# MG2639_Cellular_Shield.net
KiCad netlist of a schematic drawn in EAGLE
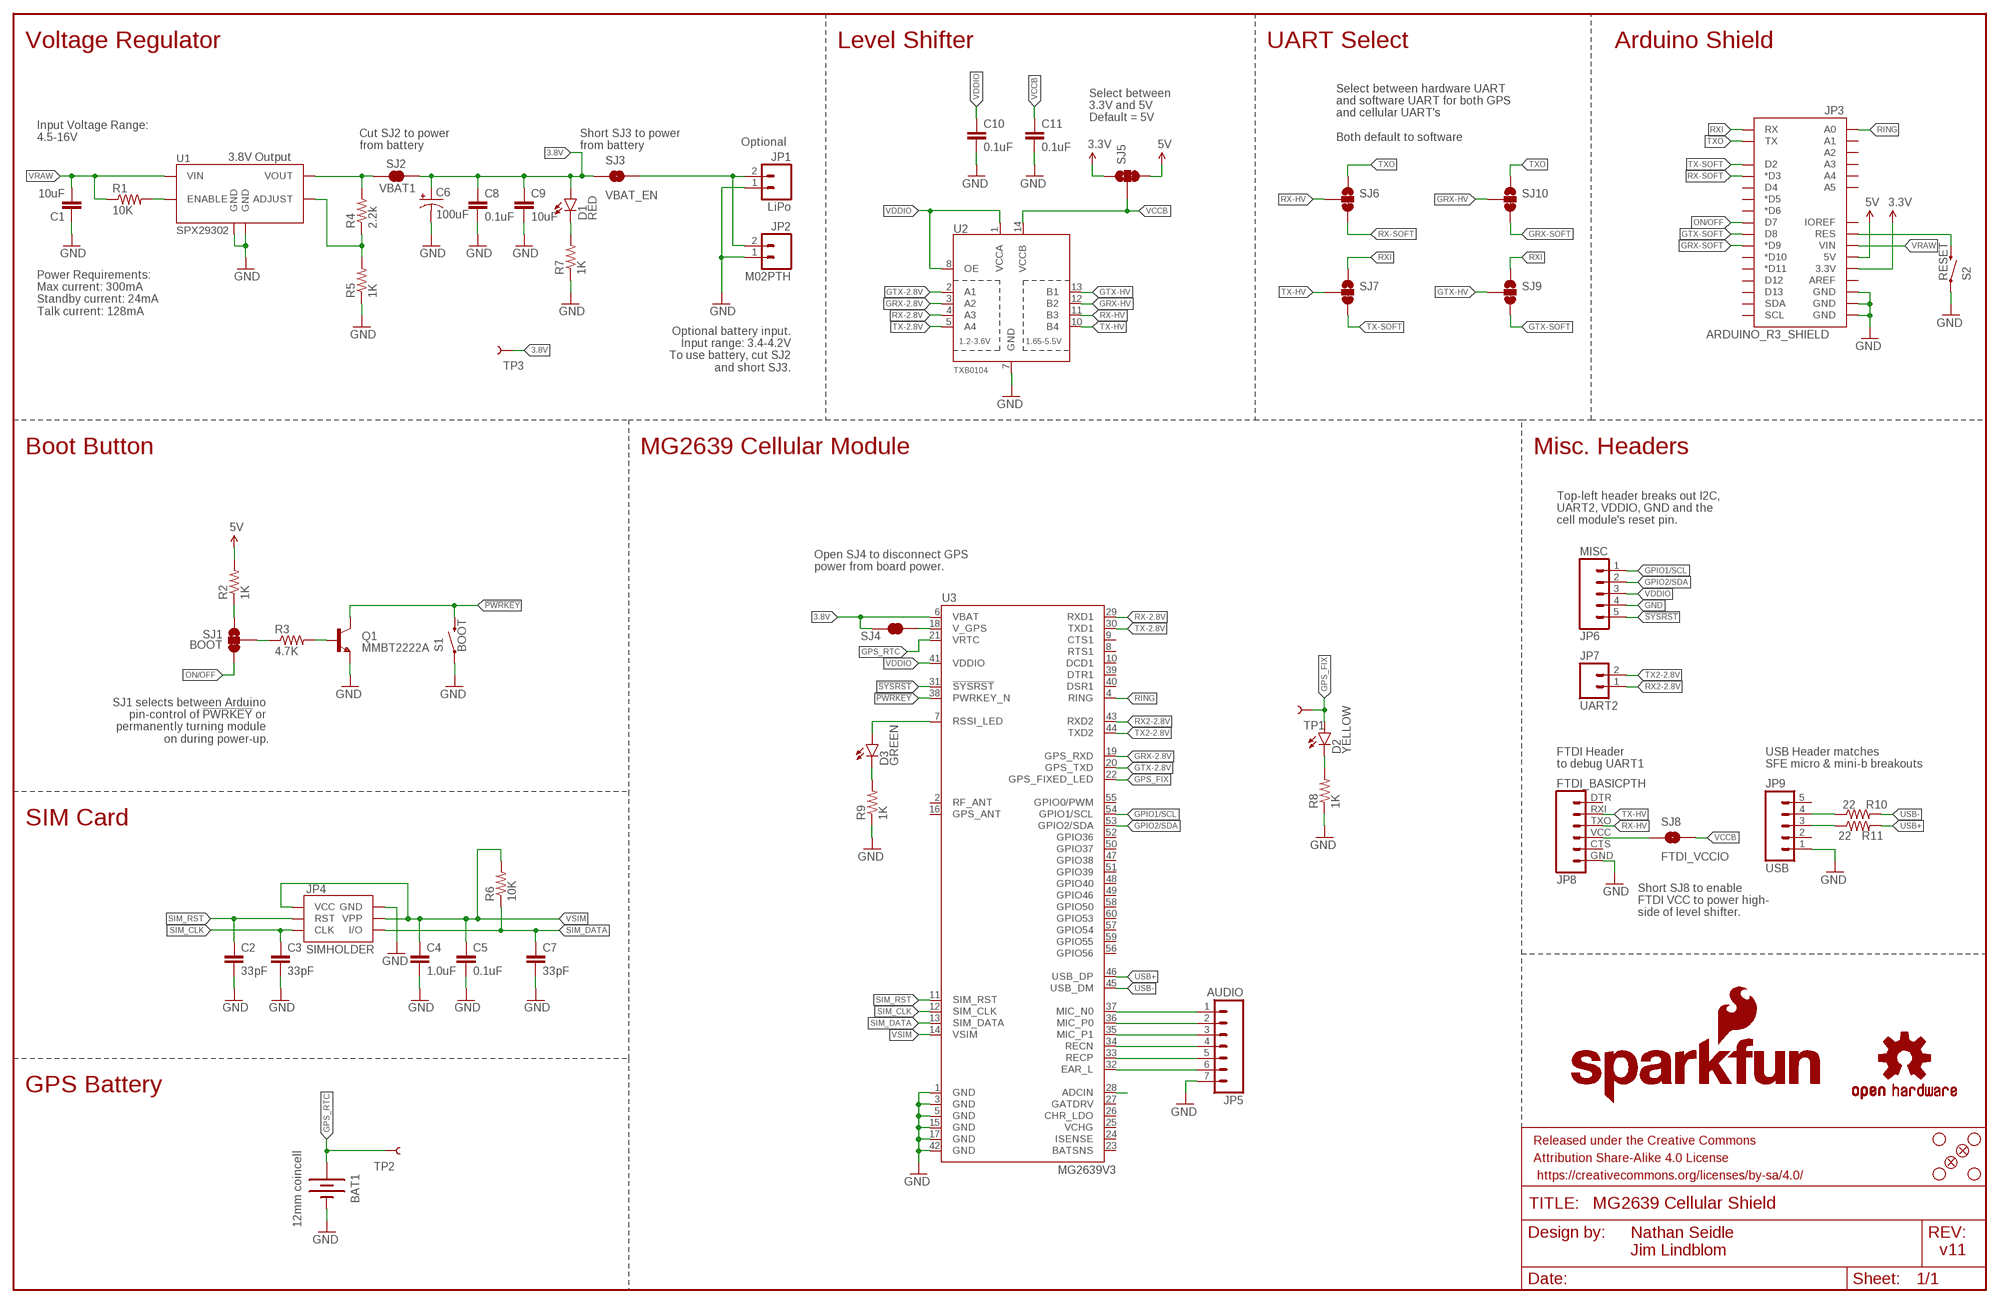
[diagram p0: schematic, sheet 1]

(export (version "E")
  (design (tool "Eeschema 10.0.6"))
  (components
    (comp (ref "BAT1")
      (value "12mm coincell")
      (footprint "eagle-import:BATTCON_12MM")
      (libsource (lib "eagle-import") (part "BATTERY12MM"))
    )
    (comp (ref "C1")
      (value "10uF")
      (footprint "eagle-import:1210")
      (libsource (lib "eagle-import") (part "10UF50V20%(1210)"))
    )
    (comp (ref "C2")
      (value "33pF")
      (footprint "eagle-import:0603-CAP")
      (libsource (lib "eagle-import") (part "33PF-50V-5%-(0603)"))
    )
    (comp (ref "C3")
      (value "33pF")
      (footprint "eagle-import:0603-CAP")
      (libsource (lib "eagle-import") (part "33PF-50V-5%-(0603)"))
    )
    (comp (ref "C4")
      (value "1.0uF")
      (footprint "eagle-import:0603-CAP")
      (libsource (lib "eagle-import") (part "1.0UF-16V-10%(0603)"))
    )
    (comp (ref "C5")
      (value "0.1uF")
      (footprint "eagle-import:0603-CAP")
      (libsource (lib "eagle-import") (part "0.1UF-25V(+80/-20%)(0603)"))
    )
    (comp (ref "C6")
      (value "100uF")
      (footprint "eagle-import:EIA7343")
      (libsource (lib "eagle-import") (part "100UF-10V-10%(TANT)"))
    )
    (comp (ref "C7")
      (value "33pF")
      (footprint "eagle-import:0603-CAP")
      (libsource (lib "eagle-import") (part "33PF-50V-5%-(0603)"))
    )
    (comp (ref "C8")
      (value "0.1uF")
      (footprint "eagle-import:0603-CAP")
      (libsource (lib "eagle-import") (part "0.1UF-25V(+80/-20%)(0603)"))
    )
    (comp (ref "C9")
      (value "10uF")
      (footprint "eagle-import:1210")
      (libsource (lib "eagle-import") (part "10UF50V20%(1210)"))
    )
    (comp (ref "C10")
      (value "0.1uF")
      (footprint "eagle-import:0603-CAP")
      (libsource (lib "eagle-import") (part "0.1UF-25V(+80/-20%)(0603)"))
    )
    (comp (ref "C11")
      (value "0.1uF")
      (footprint "eagle-import:0603-CAP")
      (libsource (lib "eagle-import") (part "0.1UF-25V(+80/-20%)(0603)"))
    )
    (comp (ref "D1")
      (value "RED")
      (footprint "eagle-import:LED-1206")
      (libsource (lib "eagle-import") (part "LED-RED1206"))
    )
    (comp (ref "D2")
      (value "YELLOW")
      (footprint "eagle-import:LED-1206")
      (libsource (lib "eagle-import") (part "LED-YELLOWLARGE"))
    )
    (comp (ref "D3")
      (value "GREEN")
      (footprint "eagle-import:LED-1206")
      (libsource (lib "eagle-import") (part "LED-GREENLARGE"))
    )
    (comp (ref "FID1")
      (value "FIDUCIAL1X2")
      (footprint "eagle-import:FIDUCIAL-1X2")
      (libsource (lib "eagle-import") (part "FIDUCIAL1X2"))
    )
    (comp (ref "FID2")
      (value "FIDUCIAL1X2")
      (footprint "eagle-import:FIDUCIAL-1X2")
      (libsource (lib "eagle-import") (part "FIDUCIAL1X2"))
    )
    (comp (ref "FRAME1")
      (value "FRAME-LEDGER")
      (footprint "eagle-import:CREATIVE_COMMONS")
      (libsource (lib "eagle-import") (part "FRAME-LEDGER"))
    )
    (comp (ref "JP1")
      (value "LiPo")
      (footprint "eagle-import:JST-2-PTH")
      (libsource (lib "eagle-import") (part "M02JST-PTH-2"))
    )
    (comp (ref "JP2")
      (value "M02PTH")
      (footprint "eagle-import:1X02")
      (libsource (lib "eagle-import") (part "M02PTH"))
    )
    (comp (ref "JP3")
      (value "ARDUINO_R3_SHIELD")
      (footprint "eagle-import:UNO_R3_SHIELD_NOLABELS")
      (libsource (lib "eagle-import") (part "ARDUINO_R3_SHIELDNOLABELS"))
    )
    (comp (ref "JP4")
      (value "SIMHOLDER")
      (footprint "eagle-import:SIMHOLDER")
      (libsource (lib "eagle-import") (part "SIMHOLDERSIM"))
    )
    (comp (ref "JP5")
      (value "AUDIO")
      (footprint "eagle-import:1X07")
      (libsource (lib "eagle-import") (part "M07"))
    )
    (comp (ref "JP6")
      (value "MISC")
      (footprint "eagle-import:1X05")
      (libsource (lib "eagle-import") (part "M05PTH"))
    )
    (comp (ref "JP7")
      (value "UART2")
      (footprint "eagle-import:1X02")
      (libsource (lib "eagle-import") (part "M02PTH"))
    )
    (comp (ref "JP8")
      (value "FTDI_BASICPTH")
      (footprint "eagle-import:FTDI_BASIC")
      (libsource (lib "eagle-import") (part "FTDI_BASICPTH"))
    )
    (comp (ref "JP9")
      (value "USB")
      (footprint "eagle-import:1X05")
      (libsource (lib "eagle-import") (part "M05PTH"))
    )
    (comp (ref "LOGO1")
      (value "SFE_LOGO_NAME.1_INCH")
      (footprint "eagle-import:SFE_LOGO_NAME_.1")
      (libsource (lib "eagle-import") (part "SFE_LOGO_NAME.1_INCH"))
    )
    (comp (ref "LOGO2")
      (value "SFE_LOGO_NAME_FLAME.2_INCH")
      (footprint "eagle-import:SFE_LOGO_NAME_FLAME_.2")
      (libsource (lib "eagle-import") (part "SFE_LOGO_NAME_FLAME.2_INCH"))
    )
    (comp (ref "LOGO3")
      (value "OSHW-LOGOS")
      (footprint "eagle-import:OSHW-LOGO-S")
      (libsource (lib "eagle-import") (part "OSHW-LOGOS"))
    )
    (comp (ref "Q1")
      (value "MMBT2222A")
      (footprint "eagle-import:SOT23-3")
      (libsource (lib "eagle-import") (part "TRANSISTOR_NPNMMBT2222A"))
    )
    (comp (ref "R1")
      (value "10K")
      (footprint "eagle-import:0603-RES")
      (libsource (lib "eagle-import") (part "10KOHM1/10W1%(0603)0603"))
    )
    (comp (ref "R2")
      (value "1K")
      (footprint "eagle-import:0603-RES")
      (libsource (lib "eagle-import") (part "1KOHM1/10W1%(0603)"))
    )
    (comp (ref "R3")
      (value "4.7K")
      (footprint "eagle-import:0603")
      (libsource (lib "eagle-import") (part "4.7KOHM1/10W1%(0603)"))
    )
    (comp (ref "R4")
      (value "2.2k")
      (footprint "eagle-import:0603-RES")
      (libsource (lib "eagle-import") (part "2.2KOHM1/10W1%(0603)"))
    )
    (comp (ref "R5")
      (value "1K")
      (footprint "eagle-import:0603-RES")
      (libsource (lib "eagle-import") (part "1KOHM1/10W1%(0603)"))
    )
    (comp (ref "R6")
      (value "10K")
      (footprint "eagle-import:0603-RES")
      (libsource (lib "eagle-import") (part "10KOHM1/10W1%(0603)0603"))
    )
    (comp (ref "R7")
      (value "1K")
      (footprint "eagle-import:0603-RES")
      (libsource (lib "eagle-import") (part "1KOHM1/10W1%(0603)"))
    )
    (comp (ref "R8")
      (value "1K")
      (footprint "eagle-import:0603-RES")
      (libsource (lib "eagle-import") (part "1KOHM1/10W1%(0603)"))
    )
    (comp (ref "R9")
      (value "1K")
      (footprint "eagle-import:0603-RES")
      (libsource (lib "eagle-import") (part "1KOHM1/10W1%(0603)"))
    )
    (comp (ref "R10")
      (value "22")
      (footprint "eagle-import:0603-RES")
      (libsource (lib "eagle-import") (part "22OHM1/10W1%(0603)"))
    )
    (comp (ref "R11")
      (value "22")
      (footprint "eagle-import:0603-RES")
      (libsource (lib "eagle-import") (part "22OHM1/10W1%(0603)"))
    )
    (comp (ref "S1")
      (value "BOOT")
      (footprint "eagle-import:TACTILE-SWITCH-SMD")
      (libsource (lib "eagle-import") (part "SWITCH-MOMENTARY-2SMD"))
    )
    (comp (ref "S2")
      (value "RESET")
      (footprint "eagle-import:TACTILE-SWITCH-SMD")
      (libsource (lib "eagle-import") (part "SWITCH-MOMENTARY-2SMD"))
    )
    (comp (ref "SJ1")
      (value "BOOT")
      (footprint "eagle-import:PAD-JUMPER-3-2OF3_NC_BY_TRACE_YES_SILK_FULL_BOX")
      (libsource (lib "eagle-import") (part "JUMPER-PAD-3-2OF3_NC_BY_TRACE"))
    )
    (comp (ref "SJ2")
      (value "VBAT1")
      (footprint "eagle-import:PAD-JUMPER-2-NC_BY_TRACE_YES_SILK")
      (libsource (lib "eagle-import") (part "JUMPER-PAD-2-NC_BY_TRACE"))
    )
    (comp (ref "SJ3")
      (value "VBAT_EN")
      (footprint "eagle-import:PAD-JUMPER-2-NO_YES_SILK")
      (libsource (lib "eagle-import") (part "JUMPER-PAD-2-NOYES_SILK"))
    )
    (comp (ref "SJ4")
      (value "JUMPER-PAD-2-NC_BY_TRACE")
      (footprint "eagle-import:PAD-JUMPER-2-NC_BY_TRACE_YES_SILK")
      (libsource (lib "eagle-import") (part "JUMPER-PAD-2-NC_BY_TRACE"))
    )
    (comp (ref "SJ5")
      (value "JUMPER-PAD-3-2OF3_NC_BY_TRACE")
      (footprint "eagle-import:PAD-JUMPER-3-2OF3_NC_BY_TRACE_YES_SILK_FULL_BOX")
      (libsource (lib "eagle-import") (part "JUMPER-PAD-3-2OF3_NC_BY_TRACE"))
    )
    (comp (ref "SJ6")
      (value "JUMPER-PAD-3-2OF3_NC_BY_TRACE")
      (footprint "eagle-import:PAD-JUMPER-3-2OF3_NC_BY_TRACE_YES_SILK_FULL_BOX")
      (libsource (lib "eagle-import") (part "JUMPER-PAD-3-2OF3_NC_BY_TRACE"))
    )
    (comp (ref "SJ7")
      (value "JUMPER-PAD-3-2OF3_NC_BY_TRACE")
      (footprint "eagle-import:PAD-JUMPER-3-2OF3_NC_BY_TRACE_YES_SILK_FULL_BOX")
      (libsource (lib "eagle-import") (part "JUMPER-PAD-3-2OF3_NC_BY_TRACE"))
    )
    (comp (ref "SJ8")
      (value "FTDI_VCCIO")
      (footprint "eagle-import:PAD-JUMPER-2-NO_YES_SILK")
      (libsource (lib "eagle-import") (part "JUMPER-PAD-2-NOYES_SILK"))
    )
    (comp (ref "SJ9")
      (value "JUMPER-PAD-3-2OF3_NC_BY_TRACE")
      (footprint "eagle-import:PAD-JUMPER-3-2OF3_NC_BY_TRACE_YES_SILK_FULL_BOX")
      (libsource (lib "eagle-import") (part "JUMPER-PAD-3-2OF3_NC_BY_TRACE"))
    )
    (comp (ref "SJ10")
      (value "JUMPER-PAD-3-2OF3_NC_BY_TRACE")
      (footprint "eagle-import:PAD-JUMPER-3-2OF3_NC_BY_TRACE_YES_SILK_FULL_BOX")
      (libsource (lib "eagle-import") (part "JUMPER-PAD-3-2OF3_NC_BY_TRACE"))
    )
    (comp (ref "STANDOFF1")
      (value "STAND-OFF")
      (footprint "eagle-import:STAND-OFF")
      (libsource (lib "eagle-import") (part "STAND-OFF"))
    )
    (comp (ref "STANDOFF2")
      (value "STAND-OFF")
      (footprint "eagle-import:STAND-OFF")
      (libsource (lib "eagle-import") (part "STAND-OFF"))
    )
    (comp (ref "STANDOFF3")
      (value "STAND-OFF")
      (footprint "eagle-import:STAND-OFF")
      (libsource (lib "eagle-import") (part "STAND-OFF"))
    )
    (comp (ref "STANDOFF4")
      (value "STAND-OFF")
      (footprint "eagle-import:STAND-OFF")
      (libsource (lib "eagle-import") (part "STAND-OFF"))
    )
    (comp (ref "TP1")
      (value "TEST-POINT3X5")
      (footprint "eagle-import:PAD.03X.05")
      (libsource (lib "eagle-import") (part "TEST-POINT3X5"))
    )
    (comp (ref "TP2")
      (value "TEST-POINT3X5")
      (footprint "eagle-import:PAD.03X.05")
      (libsource (lib "eagle-import") (part "TEST-POINT3X5"))
    )
    (comp (ref "TP3")
      (value "TEST-POINT3X5")
      (footprint "eagle-import:PAD.03X.05")
      (libsource (lib "eagle-import") (part "TEST-POINT3X5"))
    )
    (comp (ref "U1")
      (value "SPX29302")
      (footprint "eagle-import:Q5-DD_SPX29300")
      (libsource (lib "eagle-import") (part "SPX29302"))
    )
    (comp (ref "U2")
      (value "TXB0104")
      (footprint "eagle-import:SO14")
      (libsource (lib "eagle-import") (part "TXB0104PWRSOIC14"))
    )
    (comp (ref "U3")
      (value "MG2639V3")
      (footprint "eagle-import:MG2639")
      (libsource (lib "eagle-import") (part "MG2639V3"))
    )
  )
  (nets
    (net (code "1") (name "/VCHG") (class "Default")
      (node (ref "U3") (pin "25") (pinfunction "VCHG_25") (pintype "power_in"))
    )
    (net (code "2") (name "/~{PWRKEY}") (class "Default")
      (node (ref "Q1") (pin "3") (pinfunction "C_3") (pintype "passive"))
      (node (ref "S1") (pin "3") (pinfunction "2_3") (pintype "passive"))
      (node (ref "U3") (pin "38") (pinfunction "PWRKEY_N_38") (pintype "input"))
    )
    (net (code "3") (name "/~{SYSRST}") (class "Default")
      (node (ref "JP6") (pin "5") (pinfunction "5_5") (pintype "passive"))
      (node (ref "U3") (pin "31") (pinfunction "~{SYSRST}_31") (pintype "input"))
    )
    (net (code "4") (name "3.3V") (class "Default")
      (node (ref "JP3") (pin "3.3V") (pinfunction "3.3V_3.3V") (pintype "bidirectional"))
      (node (ref "SJ5") (pin "1") (pinfunction "1_1") (pintype "passive"))
    )
    (net (code "5") (name "3.8V") (class "Default")
      (node (ref "C6") (pin "A") (pinfunction "+_A") (pintype "passive"))
      (node (ref "C8") (pin "1") (pinfunction "1_1") (pintype "passive"))
      (node (ref "C9") (pin "1") (pinfunction "1_1") (pintype "passive"))
      (node (ref "D1") (pin "A") (pinfunction "A_A") (pintype "passive"))
      (node (ref "SJ2") (pin "2") (pinfunction "2_2") (pintype "passive"))
      (node (ref "SJ3") (pin "1") (pinfunction "1_1") (pintype "passive"))
      (node (ref "SJ4") (pin "1") (pinfunction "1_1") (pintype "passive"))
      (node (ref "TP3") (pin "P$1") (pinfunction "1_P$1") (pintype "bidirectional"))
      (node (ref "U3") (pin "6") (pinfunction "VBAT_6") (pintype "power_in"))
    )
    (net (code "6") (name "5V") (class "Default")
      (node (ref "JP3") (pin "5V") (pinfunction "5V_5V") (pintype "bidirectional"))
      (node (ref "R2") (pin "2") (pinfunction "2_2") (pintype "passive"))
      (node (ref "SJ5") (pin "3") (pinfunction "3_3") (pintype "passive"))
    )
    (net (code "7") (name "GND") (class "Default")
      (node (ref "BAT1") (pin "GND") (pinfunction "-_GND") (pintype "power_in"))
      (node (ref "C1") (pin "1") (pinfunction "1_1") (pintype "passive"))
      (node (ref "C10") (pin "2") (pinfunction "2_2") (pintype "passive"))
      (node (ref "C11") (pin "2") (pinfunction "2_2") (pintype "passive"))
      (node (ref "C2") (pin "2") (pinfunction "2_2") (pintype "passive"))
      (node (ref "C3") (pin "2") (pinfunction "2_2") (pintype "passive"))
      (node (ref "C4") (pin "2") (pinfunction "2_2") (pintype "passive"))
      (node (ref "C5") (pin "2") (pinfunction "2_2") (pintype "passive"))
      (node (ref "C6") (pin "C") (pinfunction "-_C") (pintype "passive"))
      (node (ref "C7") (pin "2") (pinfunction "2_2") (pintype "passive"))
      (node (ref "C8") (pin "2") (pinfunction "2_2") (pintype "passive"))
      (node (ref "C9") (pin "2") (pinfunction "2_2") (pintype "passive"))
      (node (ref "JP1") (pin "1") (pinfunction "1_1") (pintype "passive"))
      (node (ref "JP2") (pin "1") (pinfunction "1_1") (pintype "passive"))
      (node (ref "JP3") (pin "GND@0") (pinfunction "GND_GND@0") (pintype "bidirectional"))
      (node (ref "JP3") (pin "GND@1") (pinfunction "GND_GND@1") (pintype "bidirectional"))
      (node (ref "JP3") (pin "GND@2") (pinfunction "GND_GND@2") (pintype "bidirectional"))
      (node (ref "JP4") (pin "C5") (pinfunction "GND_C5") (pintype "power_in"))
      (node (ref "JP5") (pin "7") (pinfunction "7_7") (pintype "passive"))
      (node (ref "JP6") (pin "4") (pinfunction "4_4") (pintype "passive"))
      (node (ref "JP8") (pin "GND") (pinfunction "6_GND") (pintype "passive"))
      (node (ref "JP9") (pin "1") (pinfunction "1_1") (pintype "passive"))
      (node (ref "Q1") (pin "2") (pinfunction "E_2") (pintype "passive"))
      (node (ref "R5") (pin "1") (pinfunction "1_1") (pintype "passive"))
      (node (ref "R7") (pin "1") (pinfunction "1_1") (pintype "passive"))
      (node (ref "R8") (pin "1") (pinfunction "1_1") (pintype "passive"))
      (node (ref "R9") (pin "1") (pinfunction "1_1") (pintype "passive"))
      (node (ref "S1") (pin "1") (pinfunction "1_1") (pintype "passive"))
      (node (ref "S2") (pin "1") (pinfunction "1_1") (pintype "passive"))
      (node (ref "U1") (pin "3") (pinfunction "GND_3") (pintype "bidirectional"))
      (node (ref "U1") (pin "6") (pinfunction "GND_6") (pintype "bidirectional"))
      (node (ref "U2") (pin "7") (pinfunction "GND_7") (pintype "bidirectional"))
      (node (ref "U3") (pin "1") (pinfunction "GND_1") (pintype "power_in"))
      (node (ref "U3") (pin "15") (pinfunction "GND_15") (pintype "power_in"))
      (node (ref "U3") (pin "17") (pinfunction "GND_17") (pintype "power_in"))
      (node (ref "U3") (pin "3") (pinfunction "GND_3") (pintype "power_in"))
      (node (ref "U3") (pin "42") (pinfunction "GND_42") (pintype "power_in"))
      (node (ref "U3") (pin "5") (pinfunction "GND_5") (pintype "power_in"))
    )
    (net (code "8") (name "GPIO1{slash}SCL") (class "Default")
      (node (ref "JP6") (pin "1") (pinfunction "1_1") (pintype "passive"))
      (node (ref "U3") (pin "54") (pinfunction "GPIO1/SCL_54") (pintype "bidirectional"))
    )
    (net (code "9") (name "GPIO2{slash}SDA") (class "Default")
      (node (ref "JP6") (pin "2") (pinfunction "2_2") (pintype "passive"))
      (node (ref "U3") (pin "53") (pinfunction "GPIO2/SDA_53") (pintype "bidirectional"))
    )
    (net (code "10") (name "GPS_FIX") (class "Default")
      (node (ref "D2") (pin "A") (pinfunction "A_A") (pintype "passive"))
      (node (ref "TP1") (pin "P$1") (pinfunction "1_P$1") (pintype "bidirectional"))
      (node (ref "U3") (pin "22") (pinfunction "GPS_FIXED_LED_22") (pintype "output"))
    )
    (net (code "11") (name "GPS_RTC") (class "Default")
      (node (ref "BAT1") (pin "PWR@1") (pinfunction "+_PWR@1") (pintype "power_in"))
      (node (ref "TP2") (pin "P$1") (pinfunction "1_P$1") (pintype "bidirectional"))
      (node (ref "U3") (pin "21") (pinfunction "VRTC_21") (pintype "power_in"))
    )
    (net (code "12") (name "GRX-2.8V") (class "Default")
      (node (ref "U2") (pin "3") (pinfunction "A2_3") (pintype "bidirectional"))
      (node (ref "U3") (pin "19") (pinfunction "GPS_RXD_19") (pintype "input"))
    )
    (net (code "13") (name "GRX-HV") (class "Default")
      (node (ref "SJ10") (pin "2") (pinfunction "2_2") (pintype "passive"))
      (node (ref "U2") (pin "12") (pinfunction "B2_12") (pintype "bidirectional"))
    )
    (net (code "14") (name "GRX-SOFT") (class "Default")
      (node (ref "JP3") (pin "D9") (pinfunction "*D9_D9") (pintype "bidirectional"))
      (node (ref "SJ10") (pin "3") (pinfunction "3_3") (pintype "passive"))
    )
    (net (code "15") (name "GTX-2.8V") (class "Default")
      (node (ref "U2") (pin "2") (pinfunction "A1_2") (pintype "bidirectional"))
      (node (ref "U3") (pin "20") (pinfunction "GPS_TXD_20") (pintype "output"))
    )
    (net (code "16") (name "GTX-HV") (class "Default")
      (node (ref "SJ9") (pin "2") (pinfunction "2_2") (pintype "passive"))
      (node (ref "U2") (pin "13") (pinfunction "B1_13") (pintype "bidirectional"))
    )
    (net (code "17") (name "GTX-SOFT") (class "Default")
      (node (ref "JP3") (pin "D8") (pinfunction "D8_D8") (pintype "bidirectional"))
      (node (ref "SJ9") (pin "3") (pinfunction "3_3") (pintype "passive"))
    )
    (net (code "18") (name "Net-(D1-PadC)") (class "Default")
      (node (ref "D1") (pin "C") (pinfunction "C_C") (pintype "passive"))
      (node (ref "R7") (pin "2") (pinfunction "2_2") (pintype "passive"))
    )
    (net (code "19") (name "Net-(D2-PadC)") (class "Default")
      (node (ref "D2") (pin "C") (pinfunction "C_C") (pintype "passive"))
      (node (ref "R8") (pin "2") (pinfunction "2_2") (pintype "passive"))
    )
    (net (code "20") (name "Net-(D3-PadC)") (class "Default")
      (node (ref "D3") (pin "C") (pinfunction "C_C") (pintype "passive"))
      (node (ref "R9") (pin "2") (pinfunction "2_2") (pintype "passive"))
    )
    (net (code "21") (name "Net-(JP1-Pad2)") (class "Default")
      (node (ref "JP1") (pin "2") (pinfunction "2_2") (pintype "passive"))
      (node (ref "JP2") (pin "2") (pinfunction "2_2") (pintype "passive"))
      (node (ref "SJ3") (pin "2") (pinfunction "2_2") (pintype "passive"))
    )
    (net (code "22") (name "Net-(JP8-4)") (class "Default")
      (node (ref "JP8") (pin "VCC") (pinfunction "4_VCC") (pintype "passive"))
      (node (ref "SJ8") (pin "1") (pinfunction "1_1") (pintype "passive"))
    )
    (net (code "23") (name "Net-(JP9-Pad3)") (class "Default")
      (node (ref "JP9") (pin "3") (pinfunction "3_3") (pintype "passive"))
      (node (ref "R11") (pin "1") (pinfunction "1_1") (pintype "passive"))
    )
    (net (code "24") (name "Net-(JP9-Pad4)") (class "Default")
      (node (ref "JP9") (pin "4") (pinfunction "4_4") (pintype "passive"))
      (node (ref "R10") (pin "1") (pinfunction "1_1") (pintype "passive"))
    )
    (net (code "25") (name "Net-(Q1-B)") (class "Default")
      (node (ref "Q1") (pin "1") (pinfunction "B_1") (pintype "passive"))
      (node (ref "R3") (pin "2") (pinfunction "2_2") (pintype "passive"))
    )
    (net (code "26") (name "Net-(R2-Pad1)") (class "Default")
      (node (ref "R2") (pin "1") (pinfunction "1_1") (pintype "passive"))
      (node (ref "SJ1") (pin "1") (pinfunction "1_1") (pintype "passive"))
    )
    (net (code "27") (name "Net-(R3-Pad1)") (class "Default")
      (node (ref "R3") (pin "1") (pinfunction "1_1") (pintype "passive"))
      (node (ref "SJ1") (pin "2") (pinfunction "2_2") (pintype "passive"))
    )
    (net (code "28") (name "Net-(S2-2)") (class "Default")
      (node (ref "JP3") (pin "RES") (pinfunction "RES_RES") (pintype "bidirectional"))
      (node (ref "S2") (pin "3") (pinfunction "2_3") (pintype "passive"))
    )
    (net (code "29") (name "Net-(U1-ADJUST)") (class "Default")
      (node (ref "R4") (pin "1") (pinfunction "1_1") (pintype "passive"))
      (node (ref "R5") (pin "2") (pinfunction "2_2") (pintype "passive"))
      (node (ref "U1") (pin "5") (pinfunction "ADJUST_5") (pintype "bidirectional"))
    )
    (net (code "30") (name "Net-(U1-ENABLE)") (class "Default")
      (node (ref "R1") (pin "2") (pinfunction "2_2") (pintype "passive"))
      (node (ref "U1") (pin "1") (pinfunction "ENABLE_1") (pintype "bidirectional"))
    )
    (net (code "31") (name "Net-(U1-VOUT)") (class "Default")
      (node (ref "R4") (pin "2") (pinfunction "2_2") (pintype "passive"))
      (node (ref "SJ2") (pin "1") (pinfunction "1_1") (pintype "passive"))
      (node (ref "U1") (pin "4") (pinfunction "VOUT_4") (pintype "bidirectional"))
    )
    (net (code "32") (name "Net-(U3-EAR_L)") (class "Default")
      (node (ref "JP5") (pin "6") (pinfunction "6_6") (pintype "passive"))
      (node (ref "U3") (pin "32") (pinfunction "EAR_L_32") (pintype "output"))
    )
    (net (code "33") (name "Net-(U3-MIC_N0)") (class "Default")
      (node (ref "JP5") (pin "1") (pinfunction "1_1") (pintype "passive"))
      (node (ref "U3") (pin "37") (pinfunction "MIC_N0_37") (pintype "input"))
    )
    (net (code "34") (name "Net-(U3-MIC_P0)") (class "Default")
      (node (ref "JP5") (pin "2") (pinfunction "2_2") (pintype "passive"))
      (node (ref "U3") (pin "36") (pinfunction "MIC_P0_36") (pintype "input"))
    )
    (net (code "35") (name "Net-(U3-MIC_P1)") (class "Default")
      (node (ref "JP5") (pin "3") (pinfunction "3_3") (pintype "passive"))
      (node (ref "U3") (pin "35") (pinfunction "MIC_P1_35") (pintype "input"))
    )
    (net (code "36") (name "Net-(U3-RECN)") (class "Default")
      (node (ref "JP5") (pin "4") (pinfunction "4_4") (pintype "passive"))
      (node (ref "U3") (pin "34") (pinfunction "RECN_34") (pintype "output"))
    )
    (net (code "37") (name "Net-(U3-RECP)") (class "Default")
      (node (ref "JP5") (pin "5") (pinfunction "5_5") (pintype "passive"))
      (node (ref "U3") (pin "33") (pinfunction "RECP_33") (pintype "output"))
    )
    (net (code "38") (name "Net-(U3-RSSI_LED)") (class "Default")
      (node (ref "D3") (pin "A") (pinfunction "A_A") (pintype "passive"))
      (node (ref "U3") (pin "7") (pinfunction "RSSI_LED_7") (pintype "output"))
    )
    (net (code "39") (name "Net-(U3-V_GPS)") (class "Default")
      (node (ref "SJ4") (pin "2") (pinfunction "2_2") (pintype "passive"))
      (node (ref "U3") (pin "18") (pinfunction "V_GPS_18") (pintype "power_in"))
    )
    (net (code "40") (name "ON{slash}OFF") (class "Default")
      (node (ref "JP3") (pin "D7") (pinfunction "D7_D7") (pintype "bidirectional"))
      (node (ref "SJ1") (pin "3") (pinfunction "3_3") (pintype "passive"))
    )
    (net (code "41") (name "RING") (class "Default")
      (node (ref "JP3") (pin "A0") (pinfunction "A0_A0") (pintype "bidirectional"))
      (node (ref "U3") (pin "4") (pinfunction "RING_4") (pintype "output"))
    )
    (net (code "42") (name "RX-2.8V") (class "Default")
      (node (ref "U2") (pin "4") (pinfunction "A3_4") (pintype "bidirectional"))
      (node (ref "U3") (pin "29") (pinfunction "RXD1_29") (pintype "input"))
    )
    (net (code "43") (name "RX-HV") (class "Default")
      (node (ref "JP8") (pin "TXO") (pinfunction "3_TXO") (pintype "passive"))
      (node (ref "SJ6") (pin "2") (pinfunction "2_2") (pintype "passive"))
      (node (ref "U2") (pin "11") (pinfunction "B3_11") (pintype "bidirectional"))
    )
    (net (code "44") (name "RX-SOFT") (class "Default")
      (node (ref "JP3") (pin "D3") (pinfunction "*D3_D3") (pintype "bidirectional"))
      (node (ref "SJ6") (pin "3") (pinfunction "3_3") (pintype "passive"))
    )
    (net (code "45") (name "RX2-2.8V") (class "Default")
      (node (ref "JP7") (pin "1") (pinfunction "1_1") (pintype "passive"))
      (node (ref "U3") (pin "43") (pinfunction "RXD2_43") (pintype "input"))
    )
    (net (code "46") (name "RXI") (class "Default")
      (node (ref "JP3") (pin "RX") (pinfunction "RX_RX") (pintype "bidirectional"))
      (node (ref "SJ7") (pin "1") (pinfunction "1_1") (pintype "passive"))
      (node (ref "SJ9") (pin "1") (pinfunction "1_1") (pintype "passive"))
    )
    (net (code "47") (name "SIM_CLK") (class "Default")
      (node (ref "C3") (pin "1") (pinfunction "1_1") (pintype "passive"))
      (node (ref "JP4") (pin "C3") (pinfunction "CLK_C3") (pintype "input"))
      (node (ref "U3") (pin "12") (pinfunction "SIM_CLK_12") (pintype "output"))
    )
    (net (code "48") (name "SIM_DATA") (class "Default")
      (node (ref "C7") (pin "1") (pinfunction "1_1") (pintype "passive"))
      (node (ref "JP4") (pin "C7") (pinfunction "I/O_C7") (pintype "bidirectional"))
      (node (ref "R6") (pin "1") (pinfunction "1_1") (pintype "passive"))
      (node (ref "U3") (pin "13") (pinfunction "SIM_DATA_13") (pintype "bidirectional"))
    )
    (net (code "49") (name "SIM_RST") (class "Default")
      (node (ref "C2") (pin "1") (pinfunction "1_1") (pintype "passive"))
      (node (ref "JP4") (pin "C2") (pinfunction "RST_C2") (pintype "input"))
      (node (ref "U3") (pin "11") (pinfunction "SIM_RST_11") (pintype "output"))
    )
    (net (code "50") (name "TX-2.8V") (class "Default")
      (node (ref "U2") (pin "5") (pinfunction "A4_5") (pintype "bidirectional"))
      (node (ref "U3") (pin "30") (pinfunction "TXD1_30") (pintype "output"))
    )
    (net (code "51") (name "TX-HV") (class "Default")
      (node (ref "JP8") (pin "RXI") (pinfunction "2_RXI") (pintype "passive"))
      (node (ref "SJ7") (pin "2") (pinfunction "2_2") (pintype "passive"))
      (node (ref "U2") (pin "10") (pinfunction "B4_10") (pintype "bidirectional"))
    )
    (net (code "52") (name "TX-SOFT") (class "Default")
      (node (ref "JP3") (pin "D2") (pinfunction "D2_D2") (pintype "bidirectional"))
      (node (ref "SJ7") (pin "3") (pinfunction "3_3") (pintype "passive"))
    )
    (net (code "53") (name "TX2-2.8V") (class "Default")
      (node (ref "JP7") (pin "2") (pinfunction "2_2") (pintype "passive"))
      (node (ref "U3") (pin "44") (pinfunction "TXD2_44") (pintype "output"))
    )
    (net (code "54") (name "TXO") (class "Default")
      (node (ref "JP3") (pin "TX") (pinfunction "TX_TX") (pintype "bidirectional"))
      (node (ref "SJ10") (pin "1") (pinfunction "1_1") (pintype "passive"))
      (node (ref "SJ6") (pin "1") (pinfunction "1_1") (pintype "passive"))
    )
    (net (code "55") (name "USB+") (class "Default")
      (node (ref "R11") (pin "2") (pinfunction "2_2") (pintype "passive"))
      (node (ref "U3") (pin "46") (pinfunction "USB_DP_46") (pintype "bidirectional"))
    )
    (net (code "56") (name "USB-") (class "Default")
      (node (ref "R10") (pin "2") (pinfunction "2_2") (pintype "passive"))
      (node (ref "U3") (pin "45") (pinfunction "USB_DM_45") (pintype "bidirectional"))
    )
    (net (code "57") (name "VCCB") (class "Default")
      (node (ref "C11") (pin "1") (pinfunction "1_1") (pintype "passive"))
      (node (ref "SJ5") (pin "2") (pinfunction "2_2") (pintype "passive"))
      (node (ref "SJ8") (pin "2") (pinfunction "2_2") (pintype "passive"))
      (node (ref "U2") (pin "14") (pinfunction "VCCB_14") (pintype "bidirectional"))
    )
    (net (code "58") (name "VDDIO") (class "Default")
      (node (ref "C10") (pin "1") (pinfunction "1_1") (pintype "passive"))
      (node (ref "JP6") (pin "3") (pinfunction "3_3") (pintype "passive"))
      (node (ref "U2") (pin "1") (pinfunction "VCCA_1") (pintype "bidirectional"))
      (node (ref "U2") (pin "8") (pinfunction "OE_8") (pintype "bidirectional"))
      (node (ref "U3") (pin "41") (pinfunction "VDDIO_41") (pintype "output"))
    )
    (net (code "59") (name "VRAW") (class "Default")
      (node (ref "C1") (pin "2") (pinfunction "2_2") (pintype "passive"))
      (node (ref "JP3") (pin "VIN") (pinfunction "VIN_VIN") (pintype "bidirectional"))
      (node (ref "R1") (pin "1") (pinfunction "1_1") (pintype "passive"))
      (node (ref "U1") (pin "2") (pinfunction "VIN_2") (pintype "bidirectional"))
    )
    (net (code "60") (name "VSIM") (class "Default")
      (node (ref "C4") (pin "1") (pinfunction "1_1") (pintype "passive"))
      (node (ref "C5") (pin "1") (pinfunction "1_1") (pintype "passive"))
      (node (ref "JP4") (pin "C1") (pinfunction "VCC_C1") (pintype "power_in"))
      (node (ref "JP4") (pin "C6") (pinfunction "VPP_C6") (pintype "input"))
      (node (ref "R6") (pin "2") (pinfunction "2_2") (pintype "passive"))
      (node (ref "U3") (pin "14") (pinfunction "VSIM_14") (pintype "output"))
    )
    (net (code "61") (name "unconnected-(JP3-*D5-PadD5)") (class "Default")
      (node (ref "JP3") (pin "D5") (pinfunction "*D5_D5") (pintype "bidirectional"))
    )
    (net (code "62") (name "unconnected-(JP3-*D6-PadD6)") (class "Default")
      (node (ref "JP3") (pin "D6") (pinfunction "*D6_D6") (pintype "bidirectional"))
    )
    (net (code "63") (name "unconnected-(JP3-*D10-PadD10)") (class "Default")
      (node (ref "JP3") (pin "D10") (pinfunction "*D10_D10") (pintype "bidirectional"))
    )
    (net (code "64") (name "unconnected-(JP3-*D11-PadD11)") (class "Default")
      (node (ref "JP3") (pin "D11") (pinfunction "*D11_D11") (pintype "bidirectional"))
    )
    (net (code "65") (name "unconnected-(JP3-PadA1)") (class "Default")
      (node (ref "JP3") (pin "A1") (pinfunction "A1_A1") (pintype "bidirectional"))
    )
    (net (code "66") (name "unconnected-(JP3-PadA2)") (class "Default")
      (node (ref "JP3") (pin "A2") (pinfunction "A2_A2") (pintype "bidirectional"))
    )
    (net (code "67") (name "unconnected-(JP3-PadA3)") (class "Default")
      (node (ref "JP3") (pin "A3") (pinfunction "A3_A3") (pintype "bidirectional"))
    )
    (net (code "68") (name "unconnected-(JP3-PadA4)") (class "Default")
      (node (ref "JP3") (pin "A4") (pinfunction "A4_A4") (pintype "bidirectional"))
    )
    (net (code "69") (name "unconnected-(JP3-PadA5)") (class "Default")
      (node (ref "JP3") (pin "A5") (pinfunction "A5_A5") (pintype "bidirectional"))
    )
    (net (code "70") (name "unconnected-(JP3-PadAREF)") (class "Default")
      (node (ref "JP3") (pin "AREF") (pinfunction "AREF_AREF") (pintype "bidirectional"))
    )
    (net (code "71") (name "unconnected-(JP3-PadD4)") (class "Default")
      (node (ref "JP3") (pin "D4") (pinfunction "D4_D4") (pintype "bidirectional"))
    )
    (net (code "72") (name "unconnected-(JP3-PadD12)") (class "Default")
      (node (ref "JP3") (pin "D12") (pinfunction "D12_D12") (pintype "bidirectional"))
    )
    (net (code "73") (name "unconnected-(JP3-PadD13)") (class "Default")
      (node (ref "JP3") (pin "D13") (pinfunction "D13_D13") (pintype "bidirectional"))
    )
    (net (code "74") (name "unconnected-(JP3-PadIOREF)") (class "Default")
      (node (ref "JP3") (pin "IOREF") (pinfunction "IOREF_IOREF") (pintype "bidirectional"))
    )
    (net (code "75") (name "unconnected-(JP3-PadSCL)") (class "Default")
      (node (ref "JP3") (pin "SCL") (pinfunction "SCL_SCL") (pintype "bidirectional"))
    )
    (net (code "76") (name "unconnected-(JP3-PadSDA)") (class "Default")
      (node (ref "JP3") (pin "SDA") (pinfunction "SDA_SDA") (pintype "bidirectional"))
    )
    (net (code "77") (name "unconnected-(JP8-1-PadDTR)") (class "Default")
      (node (ref "JP8") (pin "DTR") (pinfunction "1_DTR") (pintype "passive"))
    )
    (net (code "78") (name "unconnected-(JP8-5-PadCTS)") (class "Default")
      (node (ref "JP8") (pin "CTS") (pinfunction "5_CTS") (pintype "passive"))
    )
    (net (code "79") (name "unconnected-(JP9-Pad2)") (class "Default")
      (node (ref "JP9") (pin "2") (pinfunction "2_2") (pintype "passive"))
    )
    (net (code "80") (name "unconnected-(JP9-Pad5)") (class "Default")
      (node (ref "JP9") (pin "5") (pinfunction "5_5") (pintype "passive"))
    )
    (net (code "81") (name "unconnected-(U3-ADCIN-Pad28)") (class "Default")
      (node (ref "U3") (pin "28") (pinfunction "ADCIN_28") (pintype "input"))
    )
    (net (code "82") (name "unconnected-(U3-BATSNS-Pad23)") (class "Default")
      (node (ref "U3") (pin "23") (pinfunction "BATSNS_23") (pintype "input"))
    )
    (net (code "83") (name "unconnected-(U3-CHR_LDO-Pad26)") (class "Default")
      (node (ref "U3") (pin "26") (pinfunction "CHR_LDO_26") (pintype "output"))
    )
    (net (code "84") (name "unconnected-(U3-CTS1-Pad9)") (class "Default")
      (node (ref "U3") (pin "9") (pinfunction "CTS1_9") (pintype "input"))
    )
    (net (code "85") (name "unconnected-(U3-DCD1-Pad10)") (class "Default")
      (node (ref "U3") (pin "10") (pinfunction "DCD1_10") (pintype "output"))
    )
    (net (code "86") (name "unconnected-(U3-DSR1-Pad40)") (class "Default")
      (node (ref "U3") (pin "40") (pinfunction "DSR1_40") (pintype "output"))
    )
    (net (code "87") (name "unconnected-(U3-DTR1-Pad39)") (class "Default")
      (node (ref "U3") (pin "39") (pinfunction "DTR1_39") (pintype "input"))
    )
    (net (code "88") (name "unconnected-(U3-GATDRV-Pad27)") (class "Default")
      (node (ref "U3") (pin "27") (pinfunction "GATDRV_27") (pintype "output"))
    )
    (net (code "89") (name "unconnected-(U3-GPIO0{slash}PWM-Pad55)") (class "Default")
      (node (ref "U3") (pin "55") (pinfunction "GPIO0/PWM_55") (pintype "bidirectional"))
    )
    (net (code "90") (name "unconnected-(U3-GPIO36-Pad52)") (class "Default")
      (node (ref "U3") (pin "52") (pinfunction "GPIO36_52") (pintype "bidirectional"))
    )
    (net (code "91") (name "unconnected-(U3-GPIO37-Pad50)") (class "Default")
      (node (ref "U3") (pin "50") (pinfunction "GPIO37_50") (pintype "bidirectional"))
    )
    (net (code "92") (name "unconnected-(U3-GPIO38-Pad47)") (class "Default")
      (node (ref "U3") (pin "47") (pinfunction "GPIO38_47") (pintype "bidirectional"))
    )
    (net (code "93") (name "unconnected-(U3-GPIO39-Pad51)") (class "Default")
      (node (ref "U3") (pin "51") (pinfunction "GPIO39_51") (pintype "bidirectional"))
    )
    (net (code "94") (name "unconnected-(U3-GPIO40-Pad48)") (class "Default")
      (node (ref "U3") (pin "48") (pinfunction "GPIO40_48") (pintype "bidirectional"))
    )
    (net (code "95") (name "unconnected-(U3-GPIO46-Pad49)") (class "Default")
      (node (ref "U3") (pin "49") (pinfunction "GPIO46_49") (pintype "bidirectional"))
    )
    (net (code "96") (name "unconnected-(U3-GPIO50-Pad58)") (class "Default")
      (node (ref "U3") (pin "58") (pinfunction "GPIO50_58") (pintype "bidirectional"))
    )
    (net (code "97") (name "unconnected-(U3-GPIO53-Pad60)") (class "Default")
      (node (ref "U3") (pin "60") (pinfunction "GPIO53_60") (pintype "bidirectional"))
    )
    (net (code "98") (name "unconnected-(U3-GPIO54-Pad57)") (class "Default")
      (node (ref "U3") (pin "57") (pinfunction "GPIO54_57") (pintype "bidirectional"))
    )
    (net (code "99") (name "unconnected-(U3-GPIO55-Pad59)") (class "Default")
      (node (ref "U3") (pin "59") (pinfunction "GPIO55_59") (pintype "bidirectional"))
    )
    (net (code "100") (name "unconnected-(U3-GPIO56-Pad56)") (class "Default")
      (node (ref "U3") (pin "56") (pinfunction "GPIO56_56") (pintype "bidirectional"))
    )
    (net (code "101") (name "unconnected-(U3-GPS_ANT-Pad16)") (class "Default")
      (node (ref "U3") (pin "16") (pinfunction "GPS_ANT_16") (pintype "input"))
    )
    (net (code "102") (name "unconnected-(U3-ISENSE-Pad24)") (class "Default")
      (node (ref "U3") (pin "24") (pinfunction "ISENSE_24") (pintype "input"))
    )
    (net (code "103") (name "unconnected-(U3-RF_ANT-Pad2)") (class "Default")
      (node (ref "U3") (pin "2") (pinfunction "RF_ANT_2") (pintype "bidirectional"))
    )
    (net (code "104") (name "unconnected-(U3-RTS1-Pad8)") (class "Default")
      (node (ref "U3") (pin "8") (pinfunction "RTS1_8") (pintype "output"))
    )
  )
)
